# QSPIFlash.net
KiCad netlist of a schematic drawn in Altium Designer
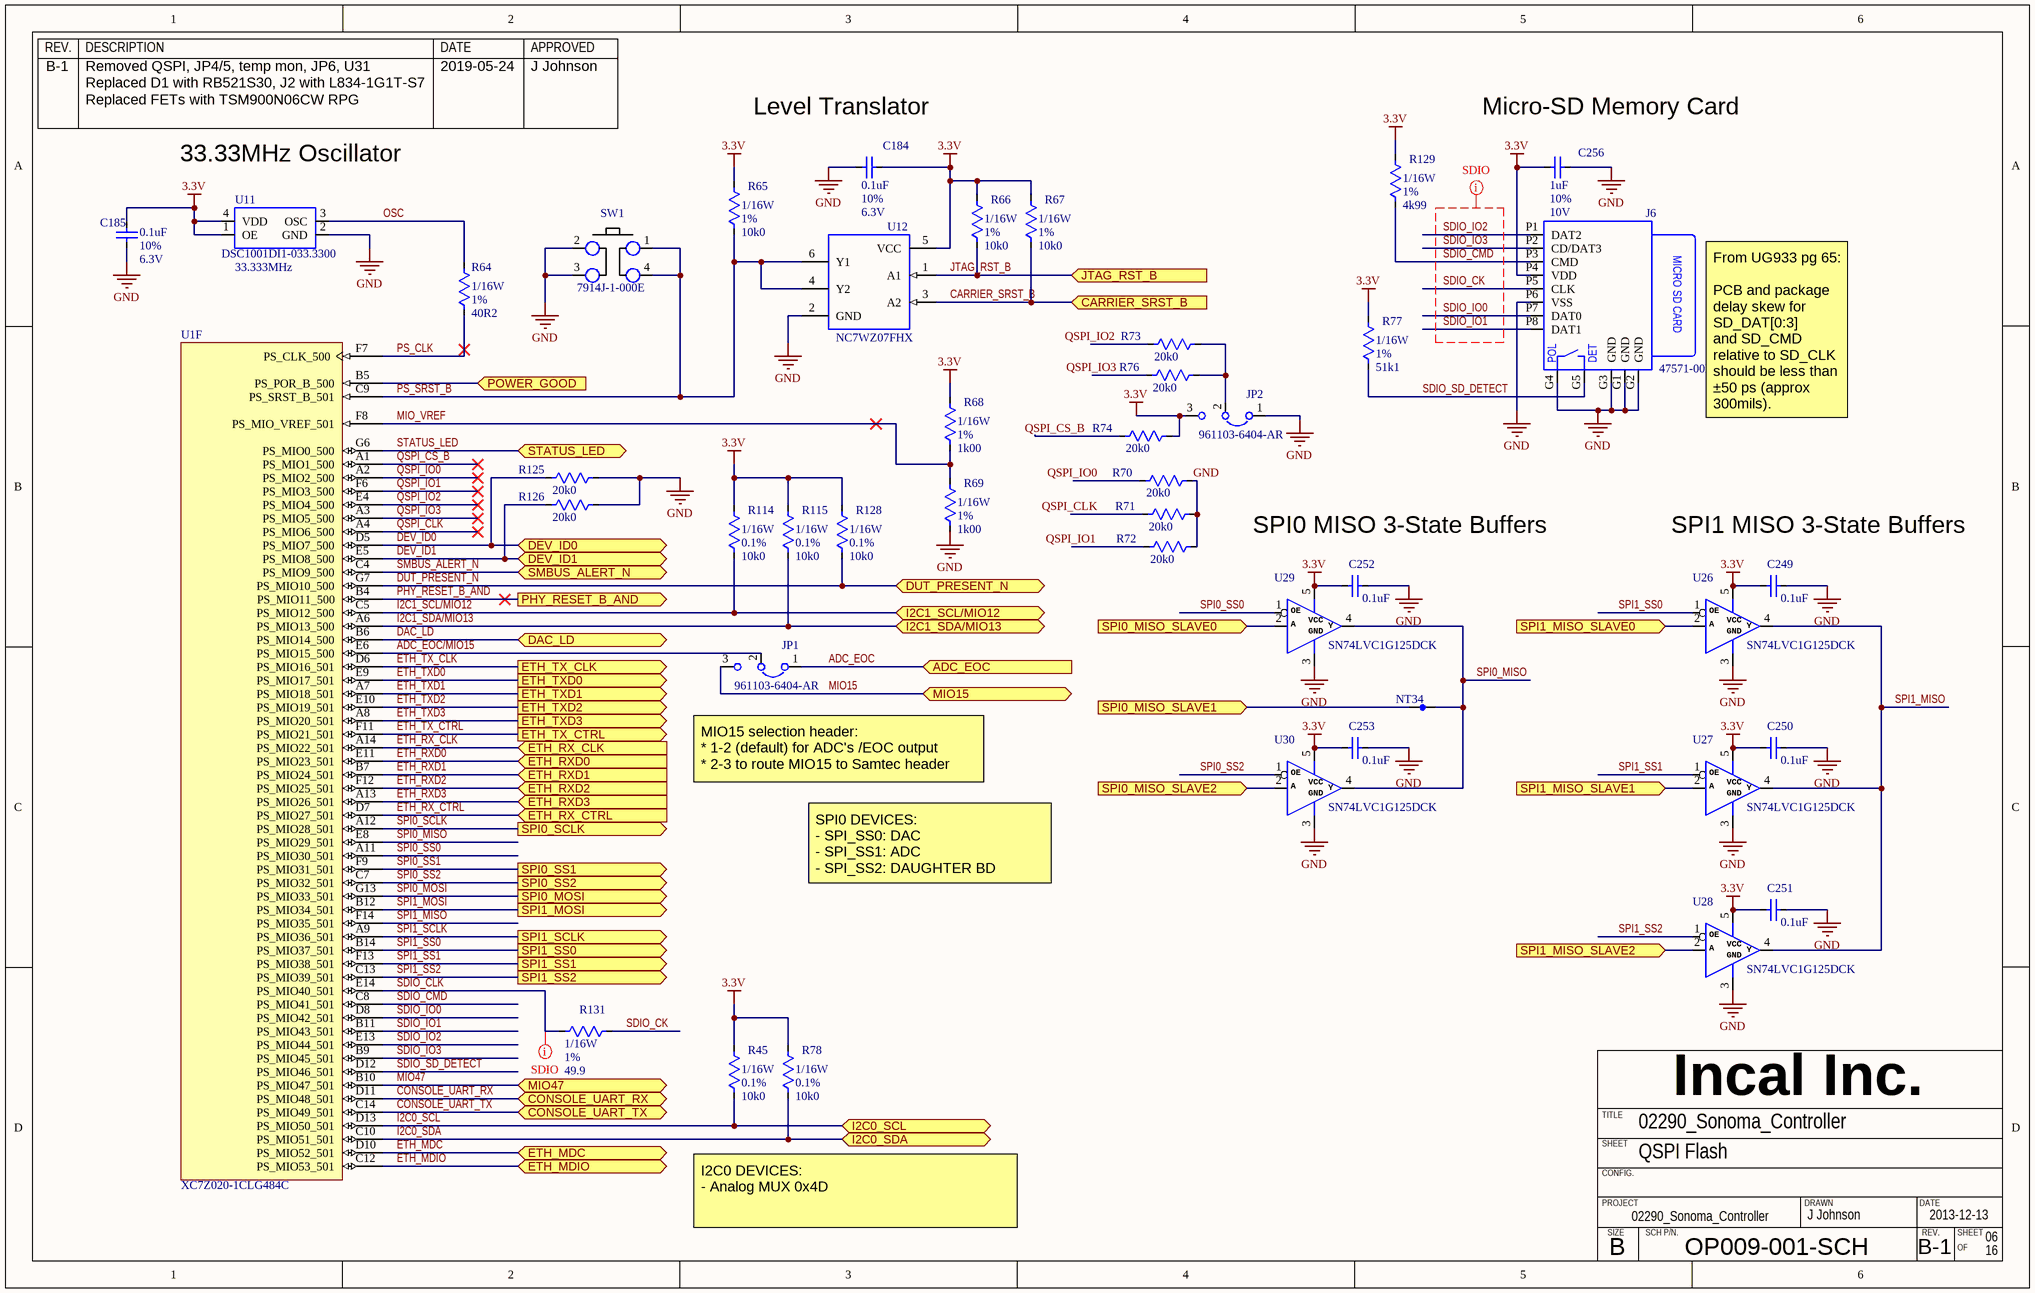
[diagram p0: QSPIFlash.SchDoc]

(export (version "E")
  (design (tool "Eeschema 10.0.6"))
  (components
    (comp (ref "C184")
      (value "0.1uF")
      (footprint "CAPC0603X33N")
      (description "Capacitor ceramic, X5R, 0.1uF, 6.3V, 10%, -55 to +125 C, EIA0201")
      (fields
        (field (name "TOLERANCE") "10%")
        (field (name "VOLTAGE") "6.3V")
        (field (name "Comment") "CAPACITOR_NP_TYPE1")
      )
      (libsource (lib "parts") (part "CAPACITOR_NP_TYPE1"))
    )
    (comp (ref "C185")
      (value "0.1uF")
      (footprint "CAPC0603X33N")
      (description "Capacitor ceramic, X5R, 0.1uF, 6.3V, 10%, -55 to +125 C, EIA0201")
      (fields
        (field (name "TOLERANCE") "10%")
        (field (name "VOLTAGE") "6.3V")
        (field (name "Comment") "CAPACITOR_NP_TYPE1")
      )
      (libsource (lib "parts") (part "CAPACITOR_NP_TYPE1"))
    )
    (comp (ref "C249")
      (value "0.1uF")
      (footprint "CAPC0603X33N")
      (description "Capacitor ceramic, X5R, 0.1uF, 6.3V, 10%, -55 to +125 C, EIA0201")
      (fields (field (name "TOLERANCE") "10%") (field (name "VOLTAGE") "6.3V"))
      (libsource (lib "parts") (part "CAPACITOR_NP_TYPE1"))
    )
    (comp (ref "C250")
      (value "0.1uF")
      (footprint "CAPC0603X33N")
      (description "Capacitor ceramic, X5R, 0.1uF, 6.3V, 10%, -55 to +125 C, EIA0201")
      (fields (field (name "TOLERANCE") "10%") (field (name "VOLTAGE") "6.3V"))
      (libsource (lib "parts") (part "CAPACITOR_NP_TYPE1"))
    )
    (comp (ref "C251")
      (value "0.1uF")
      (footprint "CAPC0603X33N")
      (description "Capacitor ceramic, X5R, 0.1uF, 6.3V, 10%, -55 to +125 C, EIA0201")
      (fields (field (name "TOLERANCE") "10%") (field (name "VOLTAGE") "6.3V"))
      (libsource (lib "parts") (part "CAPACITOR_NP_TYPE1"))
    )
    (comp (ref "C252")
      (value "0.1uF")
      (footprint "CAPC0603X33N")
      (description "Capacitor ceramic, X5R, 0.1uF, 6.3V, 10%, -55 to +125 C, EIA0201")
      (fields (field (name "TOLERANCE") "10%") (field (name "VOLTAGE") "6.3V"))
      (libsource (lib "parts") (part "CAPACITOR_NP_TYPE1"))
    )
    (comp (ref "C253")
      (value "0.1uF")
      (footprint "CAPC0603X33N")
      (description "Capacitor ceramic, X5R, 0.1uF, 6.3V, 10%, -55 to +125 C, EIA0201")
      (fields (field (name "TOLERANCE") "10%") (field (name "VOLTAGE") "6.3V"))
      (libsource (lib "parts") (part "CAPACITOR_NP_TYPE1"))
    )
    (comp (ref "C256")
      (value "1uF")
      (footprint "CAPC1005X33N")
      (description "Capacitor ceramic, X5R, 1uF, 10V, 10%, -55 to +85 C, EIA0402")
      (fields
        (field (name "TOLERANCE") "10%")
        (field (name "VOLTAGE") "10V")
        (field (name "Comment") "CAPACITOR_NP_TYPE1")
      )
      (libsource (lib "parts") (part "CAPACITOR_NP_TYPE1"))
    )
    (comp (ref "J6")
      (value "SD_MICRO_DET1")
      (footprint "47571-0001")
      (description "MicroSD Card Header with Detect, 9 pin, RA, 1.10 mm, SMT, -40 to +85C")
      (fields
        (field (name "POWER") "Pow")
        (field (name "VOLTAGE") "Vol")
        (field (name "MFG PART NUMBER 1") "47571-0001")
      )
      (libsource (lib "parts") (part "SD_MICRO_DET1"))
    )
    (comp (ref "JP1")
      (value "JP_HDR3x1_DEF1")
      (footprint "JMPR3P254_SHUNT12")
      (description "Jumper Header .100'', 3-pin, Default position 1-2, TH")
      (fields
        (field (name "POWER") "Pow")
        (field (name "VOLTAGE") "Vol")
        (field (name "MFG PART NUMBER 1") "961103-6404-AR")
      )
      (libsource (lib "parts") (part "JP_HDR3x1_DEF1"))
    )
    (comp (ref "JP2")
      (value "JP_HDR3x1_DEF1")
      (footprint "JMPR3P254_SHUNT12")
      (description "Jumper Header .100'', 3-pin, Default position 1-2, TH")
      (fields
        (field (name "POWER") "Pow")
        (field (name "VOLTAGE") "Vol")
        (field (name "MFG PART NUMBER 1") "961103-6404-AR")
      )
      (libsource (lib "parts") (part "JP_HDR3x1_DEF1"))
    )
    (comp (ref "NT34")
      (value "NET_TIE_1X1")
      (footprint "NET_TIE_1X1")
      (description "Net Tie 1 to 1")
      (libsource (lib "parts") (part "NET_TIE_1X1"))
    )
    (comp (ref "R45")
      (value "10k0")
      (footprint "RESC1005X33N")
      (description "Resistor, 10k0, 1/16W, 0.1%, -50 to +155 C, EIA0402")
      (fields (field (name "VOLTAGE") "50V") (field (name "POWER") "1/16W") (field (name "TOLERANCE") "0.1%"))
      (libsource (lib "parts") (part "RESISTOR_TYPE1"))
    )
    (comp (ref "R64")
      (value "40R2")
      (footprint "RESC1005X33N")
      (description "Resistor, 40R2, 1/16W, 1%, -50 to +155 C, EIA0402, EIA(M)1005")
      (fields (field (name "VOLTAGE") "50V") (field (name "POWER") "1/16W") (field (name "TOLERANCE") "1%"))
      (libsource (lib "parts") (part "RESISTOR_TYPE1"))
    )
    (comp (ref "R65")
      (value "10k0")
      (footprint "RESC1005X33N")
      (description "Resistor, 10k0, 1/16W, 1%, -55 to +155 C, EIA0402")
      (fields (field (name "VOLTAGE") "50V") (field (name "POWER") "1/16W") (field (name "TOLERANCE") "1%"))
      (libsource (lib "parts") (part "RESISTOR_TYPE1"))
    )
    (comp (ref "R66")
      (value "10k0")
      (footprint "RESC1005X33N")
      (description "Resistor, 10k0, 1/16W, 1%, -55 to +155 C, EIA0402")
      (fields (field (name "VOLTAGE") "50V") (field (name "POWER") "1/16W") (field (name "TOLERANCE") "1%"))
      (libsource (lib "parts") (part "RESISTOR_TYPE1"))
    )
    (comp (ref "R67")
      (value "10k0")
      (footprint "RESC1005X33N")
      (description "Resistor, 10k0, 1/16W, 1%, -55 to +155 C, EIA0402")
      (fields (field (name "VOLTAGE") "50V") (field (name "POWER") "1/16W") (field (name "TOLERANCE") "1%"))
      (libsource (lib "parts") (part "RESISTOR_TYPE1"))
    )
    (comp (ref "R68")
      (value "1k00")
      (footprint "RESC1005X33N")
      (description "Resistor, 1k00, 1/16W, 1%, -55 to +155 C, EIA0402")
      (fields (field (name "VOLTAGE") "50V") (field (name "POWER") "1/16W") (field (name "TOLERANCE") "1%"))
      (libsource (lib "parts") (part "RESISTOR_TYPE1"))
    )
    (comp (ref "R69")
      (value "1k00")
      (footprint "RESC1005X33N")
      (description "Resistor, 1k00, 1/16W, 1%, -55 to +155 C, EIA0402")
      (fields (field (name "VOLTAGE") "50V") (field (name "POWER") "1/16W") (field (name "TOLERANCE") "1%"))
      (libsource (lib "parts") (part "RESISTOR_TYPE1"))
    )
    (comp (ref "R70")
      (value "20k0")
      (footprint "RESC1005X33N")
      (description "Resistor, 20k0, 1/16W, 1%, -50 to +155 C, EIA0402, EIA(M)1005")
      (fields (field (name "VOLTAGE") "50V") (field (name "POWER") "1/16W"))
      (libsource (lib "parts") (part "RESISTOR_TYPE1"))
    )
    (comp (ref "R71")
      (value "20k0")
      (footprint "RESC1005X33N")
      (description "Resistor, 20k0, 1/16W, 1%, -50 to +155 C, EIA0402, EIA(M)1005")
      (fields (field (name "VOLTAGE") "50V") (field (name "POWER") "1/16W"))
      (libsource (lib "parts") (part "RESISTOR_TYPE1"))
    )
    (comp (ref "R72")
      (value "20k0")
      (footprint "RESC1005X33N")
      (description "Resistor, 20k0, 1/16W, 1%, -50 to +155 C, EIA0402, EIA(M)1005")
      (fields (field (name "VOLTAGE") "50V") (field (name "POWER") "1/16W"))
      (libsource (lib "parts") (part "RESISTOR_TYPE1"))
    )
    (comp (ref "R73")
      (value "20k0")
      (footprint "RESC1005X33N")
      (description "Resistor, 20k0, 1/16W, 1%, -50 to +155 C, EIA0402, EIA(M)1005")
      (fields (field (name "VOLTAGE") "50V") (field (name "POWER") "1/16W"))
      (libsource (lib "parts") (part "RESISTOR_TYPE1"))
    )
    (comp (ref "R74")
      (value "20k0")
      (footprint "RESC1005X33N")
      (description "Resistor, 20k0, 1/16W, 1%, -50 to +155 C, EIA0402, EIA(M)1005")
      (fields (field (name "VOLTAGE") "50V") (field (name "POWER") "1/16W"))
      (libsource (lib "parts") (part "RESISTOR_TYPE1"))
    )
    (comp (ref "R76")
      (value "20k0")
      (footprint "RESC1005X33N")
      (description "Resistor, 20k0, 1/16W, 1%, -50 to +155 C, EIA0402, EIA(M)1005")
      (fields (field (name "VOLTAGE") "50V") (field (name "POWER") "1/16W"))
      (libsource (lib "parts") (part "RESISTOR_TYPE1"))
    )
    (comp (ref "R77")
      (value "51k1")
      (footprint "RESC1005X33N")
      (description "Resistor, 51k1, 1/16W, 1%, -50 to +155 C, EIA0402, EIA(M)1005")
      (fields (field (name "VOLTAGE") "50V") (field (name "POWER") "1/16W") (field (name "TOLERANCE") "1%"))
      (libsource (lib "parts") (part "RESISTOR_TYPE1"))
    )
    (comp (ref "R78")
      (value "10k0")
      (footprint "RESC1005X33N")
      (description "Resistor, 10k0, 1/16W, 0.1%, -50 to +155 C, EIA0402")
      (fields (field (name "VOLTAGE") "50V") (field (name "POWER") "1/16W") (field (name "TOLERANCE") "0.1%"))
      (libsource (lib "parts") (part "RESISTOR_TYPE1"))
    )
    (comp (ref "R114")
      (value "10k0")
      (footprint "RESC1005X33N")
      (description "Resistor, 10k0, 1/16W, 0.1%, -50 to +155 C, EIA0402")
      (fields (field (name "VOLTAGE") "50V") (field (name "POWER") "1/16W") (field (name "TOLERANCE") "0.1%"))
      (libsource (lib "parts") (part "RESISTOR_TYPE1"))
    )
    (comp (ref "R115")
      (value "10k0")
      (footprint "RESC1005X33N")
      (description "Resistor, 10k0, 1/16W, 0.1%, -50 to +155 C, EIA0402")
      (fields (field (name "VOLTAGE") "50V") (field (name "POWER") "1/16W") (field (name "TOLERANCE") "0.1%"))
      (libsource (lib "parts") (part "RESISTOR_TYPE1"))
    )
    (comp (ref "R125")
      (value "20k0")
      (footprint "RESC1005X33N")
      (description "Resistor, 20k0, 1/16W, 1%, -50 to +155 C, EIA0402, EIA(M)1005")
      (fields (field (name "VOLTAGE") "50V") (field (name "POWER") "1/16W"))
      (libsource (lib "parts") (part "RESISTOR_TYPE1"))
    )
    (comp (ref "R126")
      (value "20k0")
      (footprint "RESC1005X33N")
      (description "Resistor, 20k0, 1/16W, 1%, -50 to +155 C, EIA0402, EIA(M)1005")
      (fields (field (name "VOLTAGE") "50V") (field (name "POWER") "1/16W"))
      (libsource (lib "parts") (part "RESISTOR_TYPE1"))
    )
    (comp (ref "R128")
      (value "10k0")
      (footprint "RESC1005X33N")
      (description "Resistor, 10k0, 1/16W, 0.1%, -50 to +155 C, EIA0402")
      (fields (field (name "VOLTAGE") "50V") (field (name "POWER") "1/16W") (field (name "TOLERANCE") "0.1%"))
      (libsource (lib "parts") (part "RESISTOR_TYPE1"))
    )
    (comp (ref "R129")
      (value "4k99")
      (footprint "RESC1005X33N")
      (description "Resistor, 4k99, 1/16W, 1%, -50 to +155 C, EIA0402, EIA(M)1005")
      (fields (field (name "VOLTAGE") "50V") (field (name "POWER") "1/16W") (field (name "TOLERANCE") "1%"))
      (libsource (lib "parts") (part "RESISTOR_TYPE1"))
    )
    (comp (ref "R131")
      (value "49.9")
      (footprint "RESC1005X33N")
      (description "Resistor, 51k1, 1/16W, 1%, -50 to +155 C, EIA0402, EIA(M)1005")
      (fields (field (name "VOLTAGE") "50V") (field (name "POWER") "1/16W") (field (name "TOLERANCE") "1%"))
      (libsource (lib "parts") (part "RESISTOR_TYPE1"))
    )
    (comp (ref "SW1")
      (value "7914J-1-000E")
      (footprint "7914J-1-000E")
      (description "Switch, tactile, 39V, 4mm, -55 to +125 C, SMD")
      (fields (field (name "POWER") "Pow") (field (name "VOLTAGE") "39V"))
      (libsource (lib "parts") (part "SW_SPST_TYPE1"))
    )
    (comp (ref "U1")
      (value "XC7Z020-1CLG484C")
      (footprint "CLG484")
      (description "667 MHz Zynq™-7000 AP SoC, 130 PS I/O, 200 FPGA I/O, 484-Ball BGA, Speed Grade 1, Commercial Grade")
      (fields (field (name "GENERIC PART NUMBER") "XC7Z020") (field (name "MANUFACTURER") "Xilinx"))
      (libsource (lib "parts") (part "XC7Z020-1CLG484C"))
    )
    (comp (ref "U11")
      (value "33.333MHz")
      (footprint "OSCSC165P200X250X85-4N")
      (description "Oscillator, CMOS, 33.333MHz, 50ppm, 1.7V to 3.6V, -40 to +85C, SMT")
      (fields
        (field (name "VOLTAGE") "1.7V to 3.6V")
        (field (name "MFG PART NUMBER 1") "DSC1001DI1-033.3300")
        (field (name "Comment") "OSCILLATOR_TYPE1")
      )
      (libsource (lib "parts") (part "OSCILLATOR_TYPE1"))
    )
    (comp (ref "U12")
      (value "NC7WZ07FHX")
      (footprint "DFN35P100X100X55-6N")
      (description "UHS Dual Buffer, Tiny Logic, 1.65 to 5.5V, -40 to +85 C, 200mW, MicroPak2-6")
      (fields
        (field (name "POWER") "Pow")
        (field (name "VOLTAGE") "1.65 to 5.5V")
        (field (name "MFG PART NUMBER 1") "NC7WZ07FHX")
      )
      (libsource (lib "parts") (part "NC7WZ07FHX"))
    )
    (comp (ref "U26")
      (value "SN74LVC1G125DCK")
      (footprint "SOT65P210X110-5N")
      (description "Tristate buffer, 1.65 to 5.5V, +/- 24mA, -40 to +125 C, 150mW, SC70")
      (fields (field (name "POWER") "150mW") (field (name "VOLTAGE") "1.65 to 5.5V"))
      (libsource (lib "parts") (part "TINY_SCHM_BUF_TRIS_TYPE1"))
    )
    (comp (ref "U27")
      (value "SN74LVC1G125DCK")
      (footprint "SOT65P210X110-5N")
      (description "Tristate buffer, 1.65 to 5.5V, +/- 24mA, -40 to +125 C, 150mW, SC70")
      (fields (field (name "POWER") "150mW") (field (name "VOLTAGE") "1.65 to 5.5V"))
      (libsource (lib "parts") (part "TINY_SCHM_BUF_TRIS_TYPE1"))
    )
    (comp (ref "U28")
      (value "SN74LVC1G125DCK")
      (footprint "SOT65P210X110-5N")
      (description "Tristate buffer, 1.65 to 5.5V, +/- 24mA, -40 to +125 C, 150mW, SC70")
      (fields (field (name "POWER") "150mW") (field (name "VOLTAGE") "1.65 to 5.5V"))
      (libsource (lib "parts") (part "TINY_SCHM_BUF_TRIS_TYPE1"))
    )
    (comp (ref "U29")
      (value "SN74LVC1G125DCK")
      (footprint "SOT65P210X110-5N")
      (description "Tristate buffer, 1.65 to 5.5V, +/- 24mA, -40 to +125 C, 150mW, SC70")
      (fields (field (name "POWER") "150mW") (field (name "VOLTAGE") "1.65 to 5.5V"))
      (libsource (lib "parts") (part "TINY_SCHM_BUF_TRIS_TYPE1"))
    )
    (comp (ref "U30")
      (value "SN74LVC1G125DCK")
      (footprint "SOT65P210X110-5N")
      (description "Tristate buffer, 1.65 to 5.5V, +/- 24mA, -40 to +125 C, 150mW, SC70")
      (fields (field (name "POWER") "150mW") (field (name "VOLTAGE") "1.65 to 5.5V"))
      (libsource (lib "parts") (part "TINY_SCHM_BUF_TRIS_TYPE1"))
    )
  )
  (nets
    (net (code "1") (name "/ADC_EOC") (class "Default") (node (ref "JP1") (pin "1") (pintype "passive")))
    (net (code "2") (name "/ADC_EOC{slash}MIO15") (class "Default")
      (node (ref "JP1") (pin "2") (pintype "passive"))
      (node (ref "U1") (pin "E6") (pinfunction "PS_MIO15_500_E6") (pintype "bidirectional"))
    )
    (net (code "3") (name "/CARRIER_SRST_B") (class "Default")
      (node (ref "R67") (pin "1") (pinfunction "1_1") (pintype "passive"))
      (node (ref "U12") (pin "3") (pinfunction "A2_3") (pintype "input"))
    )
    (net (code "4") (name "/CONSOLE_UART_RX") (class "Default")
      (node (ref "U1") (pin "D11") (pinfunction "PS_MIO48_501_D11") (pintype "bidirectional"))
    )
    (net (code "5") (name "/CONSOLE_UART_TX") (class "Default")
      (node (ref "U1") (pin "C14") (pinfunction "PS_MIO49_501_C14") (pintype "bidirectional"))
    )
    (net (code "6") (name "/DAC_LD") (class "Default")
      (node (ref "U1") (pin "B6") (pinfunction "PS_MIO14_500_B6") (pintype "bidirectional"))
    )
    (net (code "7") (name "/DEV_ID0") (class "Default")
      (node (ref "R125") (pin "1") (pinfunction "1_1") (pintype "passive"))
      (node (ref "U1") (pin "D5") (pinfunction "PS_MIO7_500_D5") (pintype "bidirectional"))
    )
    (net (code "8") (name "/DEV_ID1") (class "Default")
      (node (ref "R126") (pin "1") (pinfunction "1_1") (pintype "passive"))
      (node (ref "U1") (pin "E5") (pinfunction "PS_MIO8_500_E5") (pintype "bidirectional"))
    )
    (net (code "9") (name "/DUT_PRESENT_N") (class "Default")
      (node (ref "R128") (pin "2") (pinfunction "2_2") (pintype "passive"))
      (node (ref "U1") (pin "G7") (pinfunction "PS_MIO10_500_G7") (pintype "bidirectional"))
    )
    (net (code "10") (name "/ETH_MDC") (class "Default")
      (node (ref "U1") (pin "D10") (pinfunction "PS_MIO52_501_D10") (pintype "bidirectional"))
    )
    (net (code "11") (name "/ETH_MDIO") (class "Default")
      (node (ref "U1") (pin "C12") (pinfunction "PS_MIO53_501_C12") (pintype "bidirectional"))
    )
    (net (code "12") (name "/ETH_RXD0") (class "Default")
      (node (ref "U1") (pin "E11") (pinfunction "PS_MIO23_501_E11") (pintype "bidirectional"))
    )
    (net (code "13") (name "/ETH_RXD1") (class "Default")
      (node (ref "U1") (pin "B7") (pinfunction "PS_MIO24_501_B7") (pintype "bidirectional"))
    )
    (net (code "14") (name "/ETH_RXD2") (class "Default")
      (node (ref "U1") (pin "F12") (pinfunction "PS_MIO25_501_F12") (pintype "bidirectional"))
    )
    (net (code "15") (name "/ETH_RXD3") (class "Default")
      (node (ref "U1") (pin "A13") (pinfunction "PS_MIO26_501_A13") (pintype "bidirectional"))
    )
    (net (code "16") (name "/ETH_RX_CLK") (class "Default")
      (node (ref "U1") (pin "A14") (pinfunction "PS_MIO22_501_A14") (pintype "bidirectional"))
    )
    (net (code "17") (name "/ETH_RX_CTRL") (class "Default")
      (node (ref "U1") (pin "D7") (pinfunction "PS_MIO27_501_D7") (pintype "bidirectional"))
    )
    (net (code "18") (name "/ETH_TXD0") (class "Default")
      (node (ref "U1") (pin "E9") (pinfunction "PS_MIO17_501_E9") (pintype "bidirectional"))
    )
    (net (code "19") (name "/ETH_TXD1") (class "Default")
      (node (ref "U1") (pin "A7") (pinfunction "PS_MIO18_501_A7") (pintype "bidirectional"))
    )
    (net (code "20") (name "/ETH_TXD2") (class "Default")
      (node (ref "U1") (pin "E10") (pinfunction "PS_MIO19_501_E10") (pintype "bidirectional"))
    )
    (net (code "21") (name "/ETH_TXD3") (class "Default")
      (node (ref "U1") (pin "A8") (pinfunction "PS_MIO20_501_A8") (pintype "bidirectional"))
    )
    (net (code "22") (name "/ETH_TX_CLK") (class "Default")
      (node (ref "U1") (pin "D6") (pinfunction "PS_MIO16_501_D6") (pintype "bidirectional"))
    )
    (net (code "23") (name "/ETH_TX_CTRL") (class "Default")
      (node (ref "U1") (pin "F11") (pinfunction "PS_MIO21_501_F11") (pintype "bidirectional"))
    )
    (net (code "24") (name "/I2C0_SCL") (class "Default")
      (node (ref "R45") (pin "2") (pinfunction "2_2") (pintype "passive"))
      (node (ref "U1") (pin "D13") (pinfunction "PS_MIO50_501_D13") (pintype "bidirectional"))
    )
    (net (code "25") (name "/I2C0_SDA") (class "Default")
      (node (ref "R78") (pin "2") (pinfunction "2_2") (pintype "passive"))
      (node (ref "U1") (pin "C10") (pinfunction "PS_MIO51_501_C10") (pintype "bidirectional"))
    )
    (net (code "26") (name "/I2C1_SCL{slash}MIO12") (class "Default")
      (node (ref "R114") (pin "2") (pinfunction "2_2") (pintype "passive"))
      (node (ref "U1") (pin "C5") (pinfunction "PS_MIO12_500_C5") (pintype "bidirectional"))
    )
    (net (code "27") (name "/I2C1_SDA{slash}MIO13") (class "Default")
      (node (ref "R115") (pin "2") (pinfunction "2_2") (pintype "passive"))
      (node (ref "U1") (pin "A6") (pinfunction "PS_MIO13_500_A6") (pintype "bidirectional"))
    )
    (net (code "28") (name "/JTAG_RST_B") (class "Default")
      (node (ref "R66") (pin "1") (pinfunction "1_1") (pintype "passive"))
      (node (ref "U12") (pin "1") (pinfunction "A1_1") (pintype "input"))
    )
    (net (code "29") (name "/MIO15") (class "Default") (node (ref "JP1") (pin "3") (pintype "passive")))
    (net (code "30") (name "/MIO47") (class "Default")
      (node (ref "U1") (pin "B10") (pinfunction "PS_MIO47_501_B10") (pintype "bidirectional"))
    )
    (net (code "31") (name "/MIO_VREF") (class "Default")
      (node (ref "R68") (pin "2") (pinfunction "2_2") (pintype "passive"))
      (node (ref "R69") (pin "1") (pinfunction "1_1") (pintype "passive"))
      (node (ref "U1") (pin "F8") (pinfunction "PS_MIO_VREF_501_F8") (pintype "input"))
    )
    (net (code "32") (name "/OSC") (class "Default")
      (node (ref "R64") (pin "1") (pinfunction "1_1") (pintype "passive"))
      (node (ref "U11") (pin "3") (pinfunction "OSC_3") (pintype "passive"))
    )
    (net (code "33") (name "/PHY_RESET_B_AND") (class "Default")
      (node (ref "U1") (pin "B4") (pinfunction "PS_MIO11_500_B4") (pintype "bidirectional"))
    )
    (net (code "34") (name "/POWER_GOOD") (class "Default")
      (node (ref "U1") (pin "B5") (pinfunction "PS_POR_B_500_B5") (pintype "input"))
    )
    (net (code "35") (name "/PS_CLK") (class "Default")
      (node (ref "R64") (pin "2") (pinfunction "2_2") (pintype "passive"))
      (node (ref "U1") (pin "F7") (pinfunction "PS_CLK_500_F7") (pintype "input"))
    )
    (net (code "36") (name "/PS_SRST_B") (class "Default")
      (node (ref "R65") (pin "1") (pinfunction "1_1") (pintype "passive"))
      (node (ref "SW1") (pin "1") (pinfunction "1_1") (pintype "passive"))
      (node (ref "SW1") (pin "4") (pinfunction "4_4") (pintype "passive"))
      (node (ref "U1") (pin "C9") (pinfunction "PS_SRST_B_501_C9") (pintype "input"))
      (node (ref "U12") (pin "4") (pinfunction "Y2_4") (pintype "open_collector"))
      (node (ref "U12") (pin "6") (pinfunction "Y1_6") (pintype "open_collector"))
    )
    (net (code "37") (name "/QSPI_CLK") (class "Default")
      (node (ref "R71") (pin "1") (pinfunction "1_1") (pintype "passive"))
      (node (ref "U1") (pin "A4") (pinfunction "PS_MIO6_500_A4") (pintype "bidirectional"))
    )
    (net (code "38") (name "/QSPI_CS_B") (class "Default")
      (node (ref "U1") (pin "A1") (pinfunction "PS_MIO1_500_A1") (pintype "bidirectional+no_connect"))
    )
    (net (code "39") (name "/QSPI_IO0") (class "Default")
      (node (ref "R70") (pin "1") (pinfunction "1_1") (pintype "passive"))
      (node (ref "U1") (pin "A2") (pinfunction "PS_MIO2_500_A2") (pintype "bidirectional"))
    )
    (net (code "40") (name "/QSPI_IO1") (class "Default")
      (node (ref "R72") (pin "1") (pinfunction "1_1") (pintype "passive"))
      (node (ref "U1") (pin "F6") (pinfunction "PS_MIO3_500_F6") (pintype "bidirectional"))
    )
    (net (code "41") (name "/QSPI_IO2") (class "Default")
      (node (ref "R73") (pin "1") (pinfunction "1_1") (pintype "passive"))
      (node (ref "U1") (pin "E4") (pinfunction "PS_MIO4_500_E4") (pintype "bidirectional"))
    )
    (net (code "42") (name "/QSPI_IO3") (class "Default")
      (node (ref "R76") (pin "1") (pinfunction "1_1") (pintype "passive"))
      (node (ref "U1") (pin "A3") (pinfunction "PS_MIO5_500_A3") (pintype "bidirectional"))
    )
    (net (code "43") (name "/SDIO_CK") (class "Default")
      (node (ref "J6") (pin "P5") (pinfunction "CLK_P5") (pintype "passive"))
      (node (ref "R131") (pin "2") (pinfunction "2_2") (pintype "passive"))
    )
    (net (code "44") (name "/SDIO_CLK") (class "Default")
      (node (ref "R131") (pin "1") (pinfunction "1_1") (pintype "passive"))
      (node (ref "U1") (pin "E14") (pinfunction "PS_MIO40_501_E14") (pintype "bidirectional"))
    )
    (net (code "45") (name "/SDIO_CMD") (class "Default")
      (node (ref "J6") (pin "P3") (pinfunction "CMD_P3") (pintype "passive"))
      (node (ref "R129") (pin "2") (pinfunction "2_2") (pintype "passive"))
      (node (ref "U1") (pin "C8") (pinfunction "PS_MIO41_501_C8") (pintype "bidirectional"))
    )
    (net (code "46") (name "/SDIO_IO0") (class "Default")
      (node (ref "J6") (pin "P7") (pinfunction "DAT0_P7") (pintype "passive"))
      (node (ref "U1") (pin "D8") (pinfunction "PS_MIO42_501_D8") (pintype "bidirectional"))
    )
    (net (code "47") (name "/SDIO_IO1") (class "Default")
      (node (ref "J6") (pin "P8") (pinfunction "DAT1_P8") (pintype "passive"))
      (node (ref "U1") (pin "B11") (pinfunction "PS_MIO43_501_B11") (pintype "bidirectional"))
    )
    (net (code "48") (name "/SDIO_IO2") (class "Default")
      (node (ref "J6") (pin "P1") (pinfunction "DAT2_P1") (pintype "passive"))
      (node (ref "U1") (pin "E13") (pinfunction "PS_MIO44_501_E13") (pintype "bidirectional"))
    )
    (net (code "49") (name "/SDIO_IO3") (class "Default")
      (node (ref "J6") (pin "P2") (pinfunction "CD/DAT3_P2") (pintype "passive"))
      (node (ref "U1") (pin "B9") (pinfunction "PS_MIO45_501_B9") (pintype "bidirectional"))
    )
    (net (code "50") (name "/SDIO_SD_DETECT") (class "Default")
      (node (ref "J6") (pin "G5") (pinfunction "DET_G5") (pintype "passive"))
      (node (ref "R77") (pin "2") (pinfunction "2_2") (pintype "passive"))
      (node (ref "U1") (pin "D12") (pinfunction "PS_MIO46_501_D12") (pintype "bidirectional"))
    )
    (net (code "51") (name "/SMBUS_ALERT_N") (class "Default")
      (node (ref "U1") (pin "C4") (pinfunction "PS_MIO9_500_C4") (pintype "bidirectional"))
    )
    (net (code "52") (name "/SPI0_MISO") (class "Default")
      (node (ref "NT34") (pin "2") (pinfunction "2_2") (pintype "passive"))
      (node (ref "U1") (pin "E8") (pinfunction "PS_MIO29_501_E8") (pintype "bidirectional"))
      (node (ref "U29") (pin "4") (pinfunction "Y_4") (pintype "passive"))
      (node (ref "U30") (pin "4") (pinfunction "Y_4") (pintype "passive"))
    )
    (net (code "53") (name "/SPI0_MISO_SLAVE0") (class "Default")
      (node (ref "U29") (pin "2") (pinfunction "A_2") (pintype "passive"))
    )
    (net (code "54") (name "/SPI0_MISO_SLAVE1") (class "Default")
      (node (ref "NT34") (pin "1") (pinfunction "1_1") (pintype "passive"))
    )
    (net (code "55") (name "/SPI0_MISO_SLAVE2") (class "Default")
      (node (ref "U30") (pin "2") (pinfunction "A_2") (pintype "passive"))
    )
    (net (code "56") (name "/SPI0_MOSI") (class "Default")
      (node (ref "U1") (pin "G13") (pinfunction "PS_MIO33_501_G13") (pintype "bidirectional"))
    )
    (net (code "57") (name "/SPI0_SCLK") (class "Default")
      (node (ref "U1") (pin "A12") (pinfunction "PS_MIO28_501_A12") (pintype "bidirectional"))
    )
    (net (code "58") (name "/SPI0_SS0") (class "Default")
      (node (ref "U1") (pin "A11") (pinfunction "PS_MIO30_501_A11") (pintype "bidirectional"))
      (node (ref "U29") (pin "1") (pinfunction "OE_1") (pintype "passive"))
    )
    (net (code "59") (name "/SPI0_SS1") (class "Default")
      (node (ref "U1") (pin "F9") (pinfunction "PS_MIO31_501_F9") (pintype "bidirectional"))
    )
    (net (code "60") (name "/SPI0_SS2") (class "Default")
      (node (ref "U1") (pin "C7") (pinfunction "PS_MIO32_501_C7") (pintype "bidirectional"))
      (node (ref "U30") (pin "1") (pinfunction "OE_1") (pintype "passive"))
    )
    (net (code "61") (name "/SPI1_MISO") (class "Default")
      (node (ref "U1") (pin "F14") (pinfunction "PS_MIO35_501_F14") (pintype "bidirectional"))
      (node (ref "U26") (pin "4") (pinfunction "Y_4") (pintype "passive"))
      (node (ref "U27") (pin "4") (pinfunction "Y_4") (pintype "passive"))
      (node (ref "U28") (pin "4") (pinfunction "Y_4") (pintype "passive"))
    )
    (net (code "62") (name "/SPI1_MISO_SLAVE0") (class "Default")
      (node (ref "U26") (pin "2") (pinfunction "A_2") (pintype "passive"))
    )
    (net (code "63") (name "/SPI1_MISO_SLAVE1") (class "Default")
      (node (ref "U27") (pin "2") (pinfunction "A_2") (pintype "passive"))
    )
    (net (code "64") (name "/SPI1_MISO_SLAVE2") (class "Default")
      (node (ref "U28") (pin "2") (pinfunction "A_2") (pintype "passive"))
    )
    (net (code "65") (name "/SPI1_MOSI") (class "Default")
      (node (ref "U1") (pin "B12") (pinfunction "PS_MIO34_501_B12") (pintype "bidirectional"))
    )
    (net (code "66") (name "/SPI1_SCLK") (class "Default")
      (node (ref "U1") (pin "A9") (pinfunction "PS_MIO36_501_A9") (pintype "bidirectional"))
    )
    (net (code "67") (name "/SPI1_SS0") (class "Default")
      (node (ref "U1") (pin "B14") (pinfunction "PS_MIO37_501_B14") (pintype "bidirectional"))
      (node (ref "U26") (pin "1") (pinfunction "OE_1") (pintype "passive"))
    )
    (net (code "68") (name "/SPI1_SS1") (class "Default")
      (node (ref "U1") (pin "F13") (pinfunction "PS_MIO38_501_F13") (pintype "bidirectional"))
      (node (ref "U27") (pin "1") (pinfunction "OE_1") (pintype "passive"))
    )
    (net (code "69") (name "/SPI1_SS2") (class "Default")
      (node (ref "U1") (pin "C13") (pinfunction "PS_MIO39_501_C13") (pintype "bidirectional"))
      (node (ref "U28") (pin "1") (pinfunction "OE_1") (pintype "passive"))
    )
    (net (code "70") (name "/STATUS_LED") (class "Default")
      (node (ref "U1") (pin "G6") (pinfunction "PS_MIO0_500_G6") (pintype "bidirectional"))
    )
    (net (code "71") (name "3.3V") (class "Default")
      (node (ref "C184") (pin "1") (pinfunction "1_1") (pintype "passive"))
      (node (ref "C185") (pin "1") (pinfunction "1_1") (pintype "passive"))
      (node (ref "C249") (pin "1") (pinfunction "1_1") (pintype "passive"))
      (node (ref "C250") (pin "1") (pinfunction "1_1") (pintype "passive"))
      (node (ref "C251") (pin "1") (pinfunction "1_1") (pintype "passive"))
      (node (ref "C252") (pin "1") (pinfunction "1_1") (pintype "passive"))
      (node (ref "C253") (pin "1") (pinfunction "1_1") (pintype "passive"))
      (node (ref "C256") (pin "1") (pinfunction "1_1") (pintype "passive"))
      (node (ref "J6") (pin "P4") (pinfunction "VDD_P4") (pintype "passive"))
      (node (ref "JP2") (pin "3") (pintype "passive"))
      (node (ref "R114") (pin "1") (pinfunction "1_1") (pintype "passive"))
      (node (ref "R115") (pin "1") (pinfunction "1_1") (pintype "passive"))
      (node (ref "R128") (pin "1") (pinfunction "1_1") (pintype "passive"))
      (node (ref "R129") (pin "1") (pinfunction "1_1") (pintype "passive"))
      (node (ref "R45") (pin "1") (pinfunction "1_1") (pintype "passive"))
      (node (ref "R65") (pin "2") (pinfunction "2_2") (pintype "passive"))
      (node (ref "R66") (pin "2") (pinfunction "2_2") (pintype "passive"))
      (node (ref "R67") (pin "2") (pinfunction "2_2") (pintype "passive"))
      (node (ref "R68") (pin "1") (pinfunction "1_1") (pintype "passive"))
      (node (ref "R74") (pin "2") (pinfunction "2_2") (pintype "passive"))
      (node (ref "R77") (pin "1") (pinfunction "1_1") (pintype "passive"))
      (node (ref "R78") (pin "1") (pinfunction "1_1") (pintype "passive"))
      (node (ref "U11") (pin "1") (pinfunction "OE_1") (pintype "passive"))
      (node (ref "U11") (pin "4") (pinfunction "VDD_4") (pintype "passive"))
      (node (ref "U12") (pin "5") (pinfunction "VCC_5") (pintype "power_in"))
      (node (ref "U26") (pin "5") (pinfunction "VCC_5") (pintype "passive"))
      (node (ref "U27") (pin "5") (pinfunction "VCC_5") (pintype "passive"))
      (node (ref "U28") (pin "5") (pinfunction "VCC_5") (pintype "passive"))
      (node (ref "U29") (pin "5") (pinfunction "VCC_5") (pintype "passive"))
      (node (ref "U30") (pin "5") (pinfunction "VCC_5") (pintype "passive"))
    )
    (net (code "72") (name "GND") (class "Default")
      (node (ref "C184") (pin "2") (pinfunction "2_2") (pintype "passive"))
      (node (ref "C185") (pin "2") (pinfunction "2_2") (pintype "passive"))
      (node (ref "C249") (pin "2") (pinfunction "2_2") (pintype "passive"))
      (node (ref "C250") (pin "2") (pinfunction "2_2") (pintype "passive"))
      (node (ref "C251") (pin "2") (pinfunction "2_2") (pintype "passive"))
      (node (ref "C252") (pin "2") (pinfunction "2_2") (pintype "passive"))
      (node (ref "C253") (pin "2") (pinfunction "2_2") (pintype "passive"))
      (node (ref "C256") (pin "2") (pinfunction "2_2") (pintype "passive"))
      (node (ref "J6") (pin "G1") (pinfunction "GND_G1") (pintype "passive"))
      (node (ref "J6") (pin "G2") (pinfunction "GND_G2") (pintype "passive"))
      (node (ref "J6") (pin "G3") (pinfunction "GND_G3") (pintype "passive"))
      (node (ref "J6") (pin "G4") (pinfunction "POL_G4") (pintype "passive"))
      (node (ref "J6") (pin "P6") (pinfunction "VSS_P6") (pintype "passive"))
      (node (ref "JP2") (pin "1") (pintype "passive"))
      (node (ref "R125") (pin "2") (pinfunction "2_2") (pintype "passive"))
      (node (ref "R126") (pin "2") (pinfunction "2_2") (pintype "passive"))
      (node (ref "R69") (pin "2") (pinfunction "2_2") (pintype "passive"))
      (node (ref "R70") (pin "2") (pinfunction "2_2") (pintype "passive"))
      (node (ref "R71") (pin "2") (pinfunction "2_2") (pintype "passive"))
      (node (ref "R72") (pin "2") (pinfunction "2_2") (pintype "passive"))
      (node (ref "SW1") (pin "2") (pinfunction "2_2") (pintype "passive"))
      (node (ref "SW1") (pin "3") (pinfunction "3_3") (pintype "passive"))
      (node (ref "U11") (pin "2") (pinfunction "GND_2") (pintype "passive"))
      (node (ref "U12") (pin "2") (pinfunction "GND_2") (pintype "power_in"))
      (node (ref "U26") (pin "3") (pinfunction "GND_3") (pintype "passive"))
      (node (ref "U27") (pin "3") (pinfunction "GND_3") (pintype "passive"))
      (node (ref "U28") (pin "3") (pinfunction "GND_3") (pintype "passive"))
      (node (ref "U29") (pin "3") (pinfunction "GND_3") (pintype "passive"))
      (node (ref "U30") (pin "3") (pinfunction "GND_3") (pintype "passive"))
    )
    (net (code "73") (name "Net-(JP2-Pad2)") (class "Default")
      (node (ref "JP2") (pin "2") (pintype "passive"))
      (node (ref "R73") (pin "2") (pinfunction "2_2") (pintype "passive"))
      (node (ref "R76") (pin "2") (pinfunction "2_2") (pintype "passive"))
    )
    (net (code "74") (name "unconnected-(R74-Pad1)") (class "Default")
      (node (ref "R74") (pin "1") (pinfunction "1_1") (pintype "passive"))
    )
  )
)
